# DebugCAN_v3.net
KiCad netlist of a schematic drawn in EAGLE
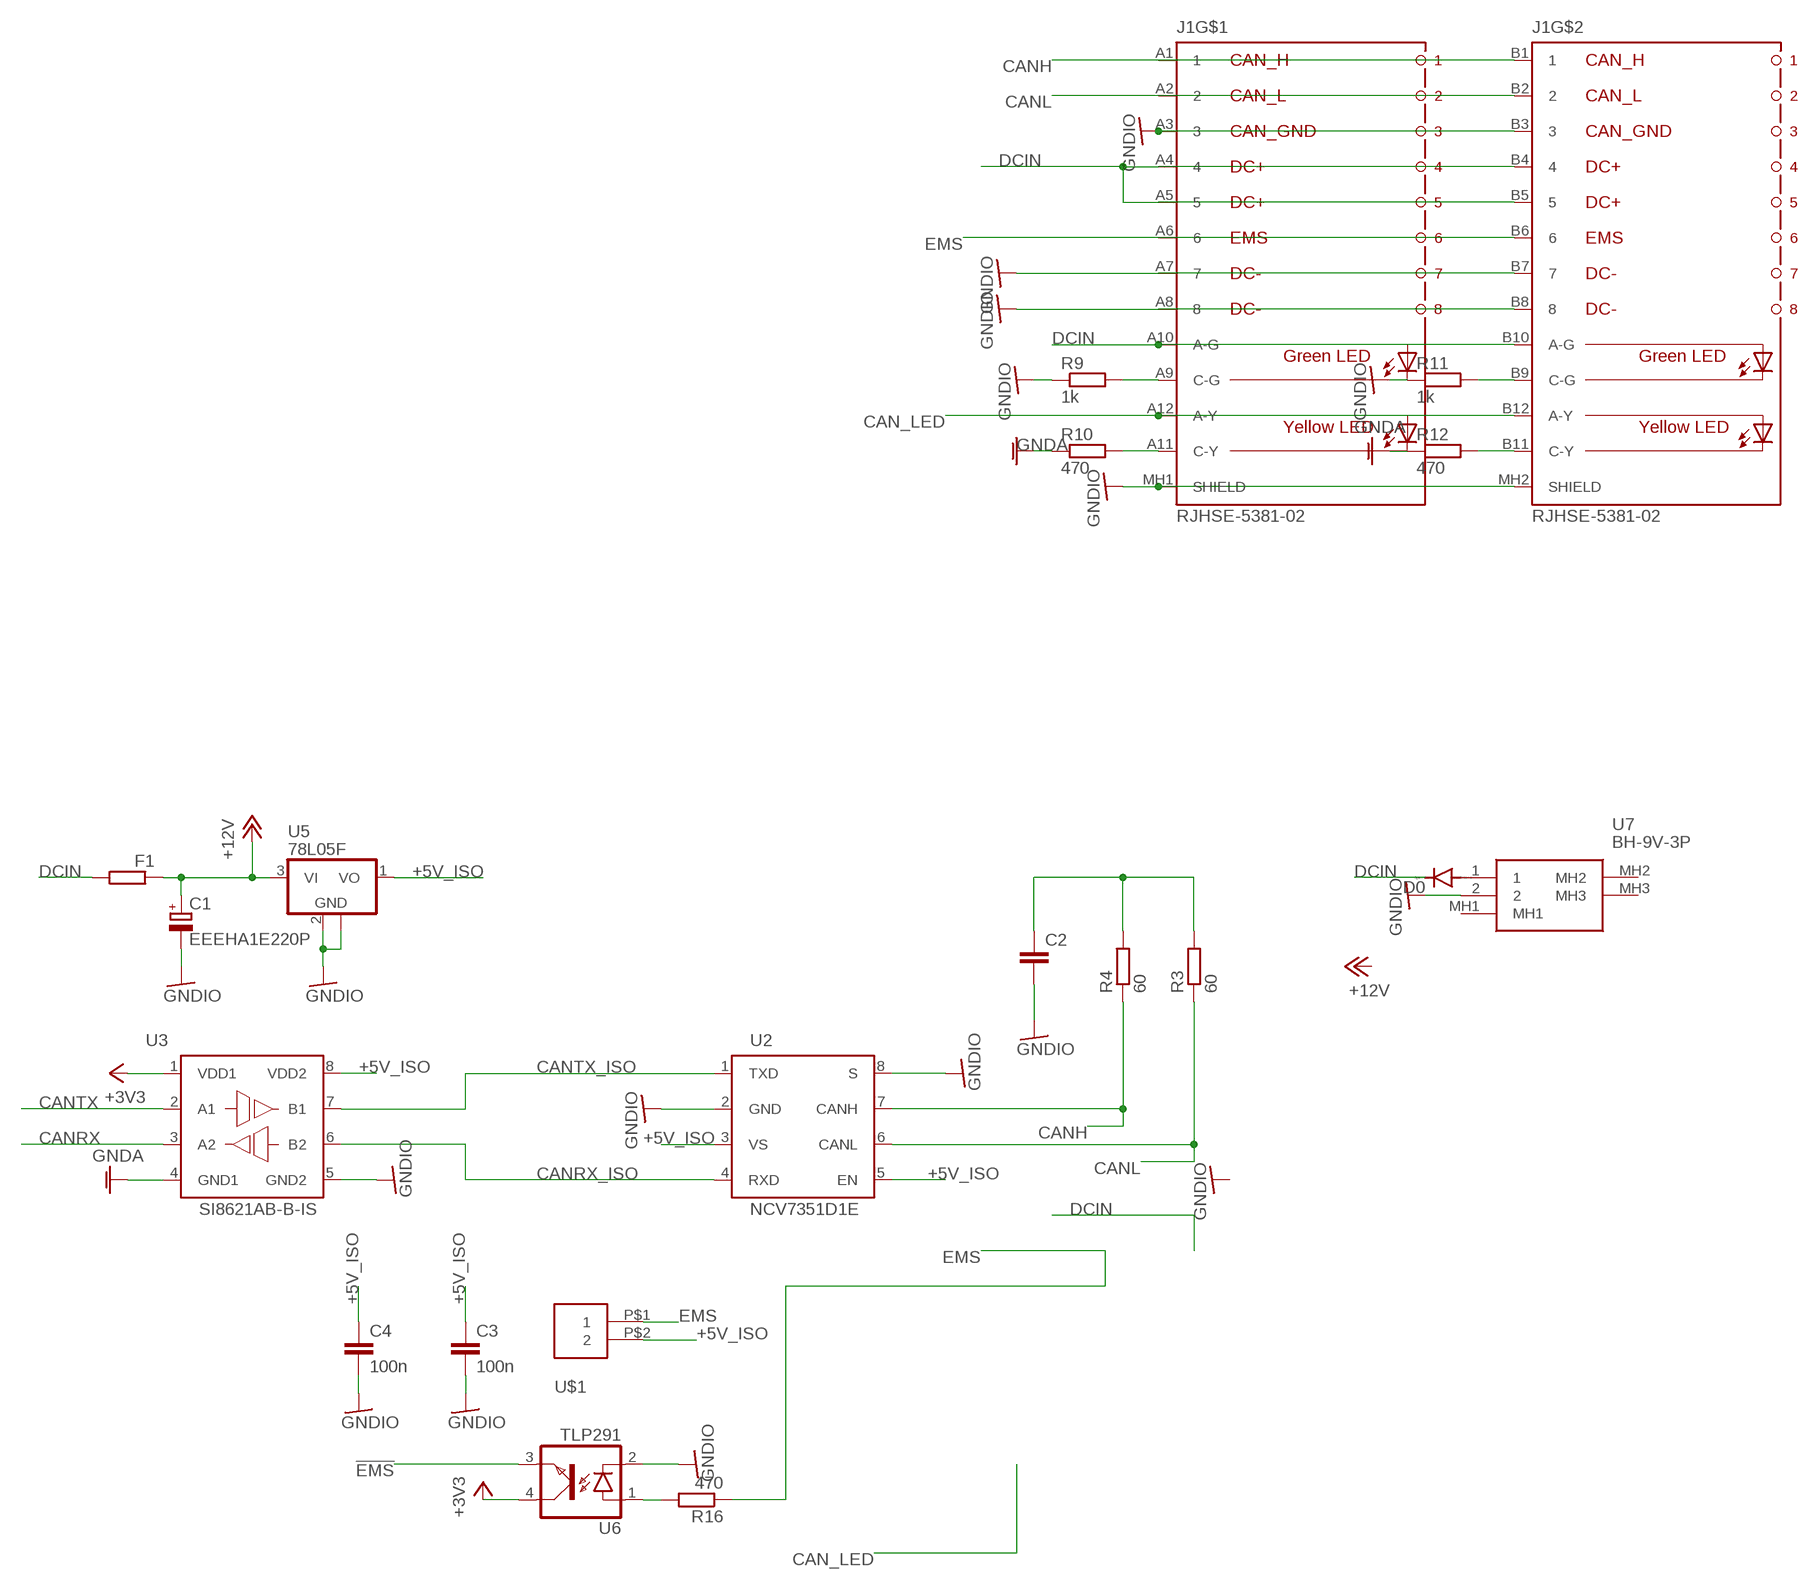
[diagram p0: schematic, sheet 1]
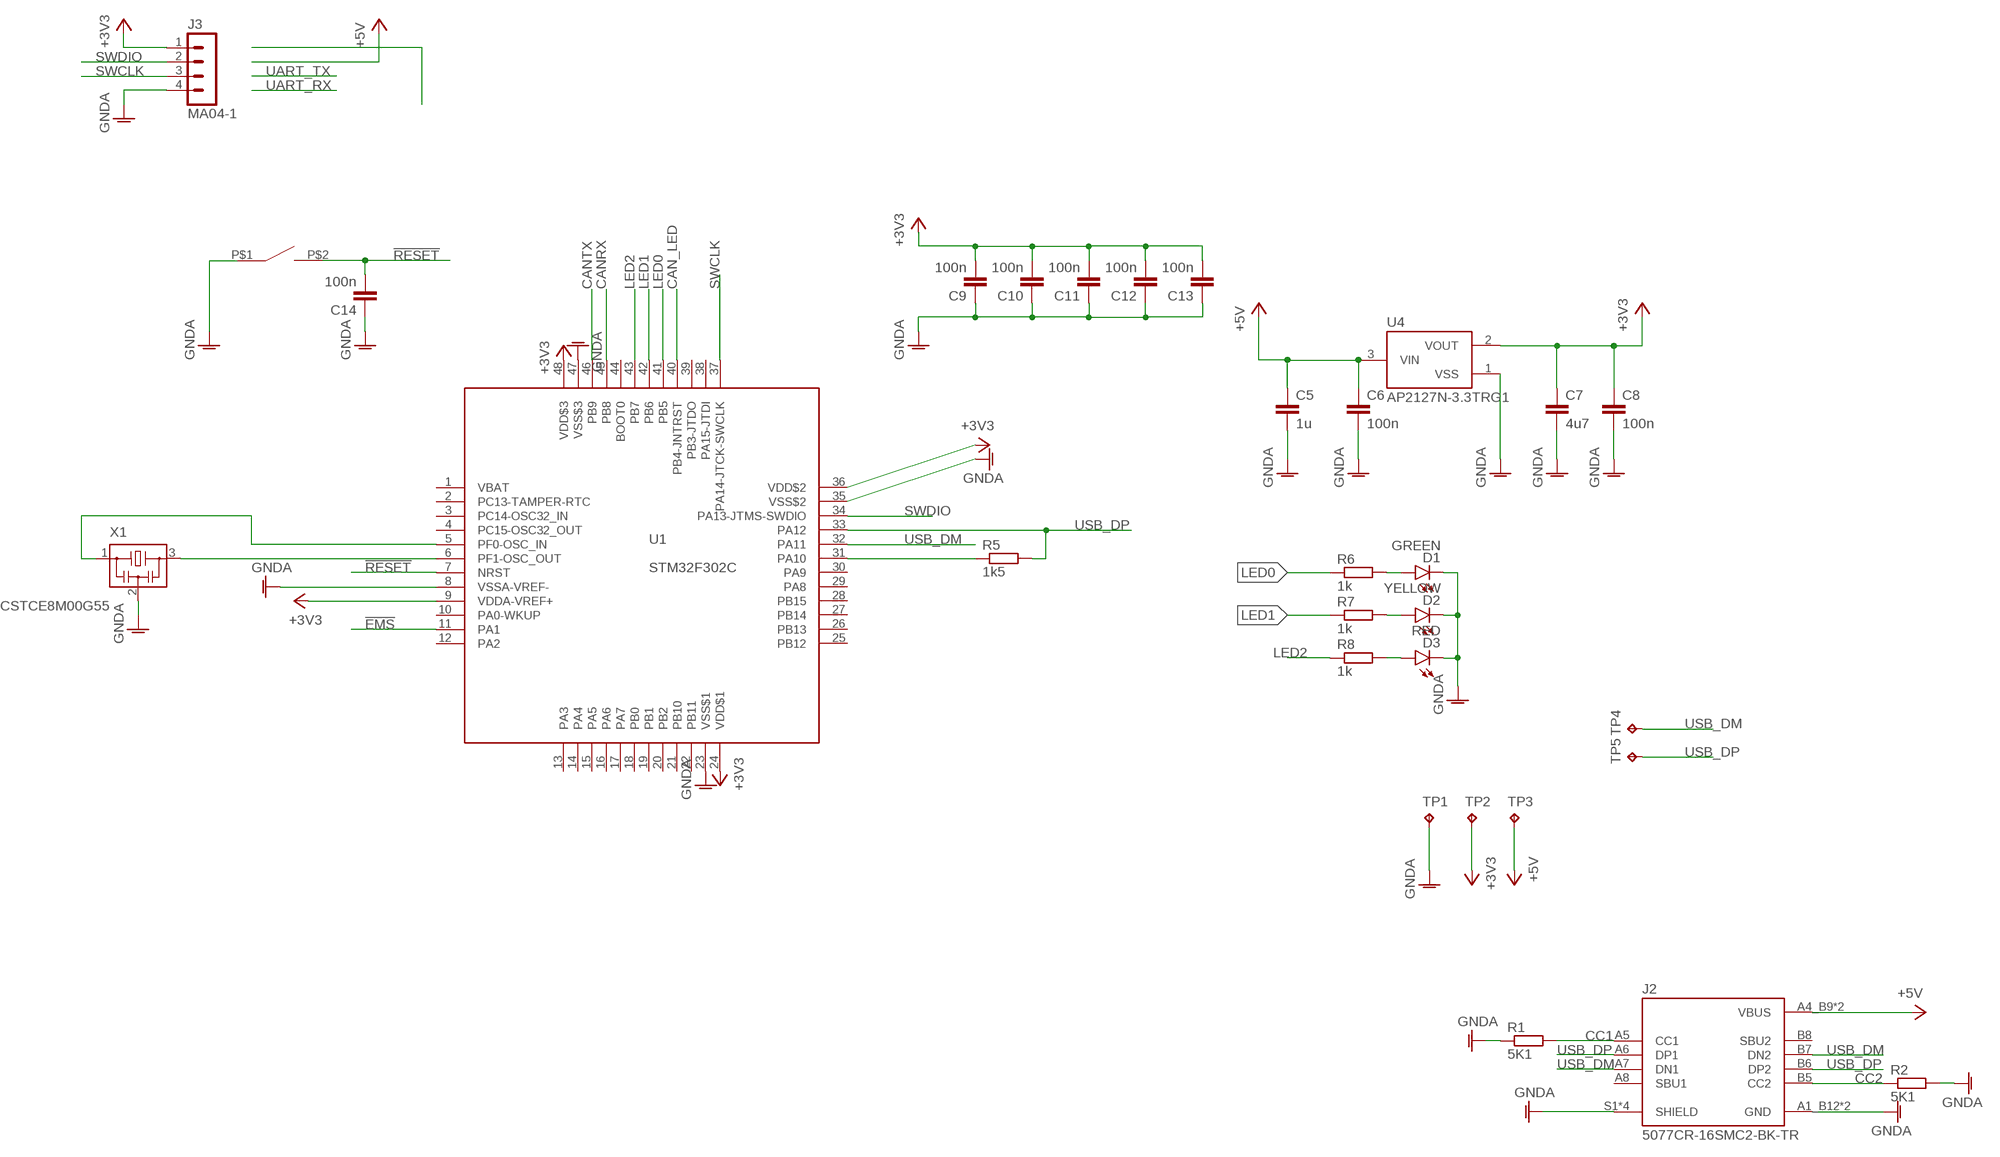
[diagram p1: schematic, sheet 2]

(export (version "E")
  (design (tool "Eeschema 10.0.6"))
  (components
    (comp (ref "C1")
      (value "EEEHA1E220P")
      (footprint "eagle-import:153CLV-0605")
      (libsource (lib "eagle-import") (part "CPOL-EU153CLV-0605"))
    )
    (comp (ref "C2")
      (value "C-EUC0603")
      (footprint "eagle-import:C0603")
      (libsource (lib "eagle-import") (part "rcl_334_C-EUC0603"))
    )
    (comp (ref "C3")
      (value "100n")
      (footprint "eagle-import:C0603")
      (libsource (lib "eagle-import") (part "rcl_334_C-EUC0603"))
    )
    (comp (ref "C4")
      (value "100n")
      (footprint "eagle-import:C0603")
      (libsource (lib "eagle-import") (part "rcl_334_C-EUC0603"))
    )
    (comp (ref "D0")
      (value "DIODE-SOD123")
      (footprint "eagle-import:SOD123")
      (libsource (lib "eagle-import") (part "DIODE-SOD123"))
    )
    (comp (ref "F1")
      (value "R-EU_R1206")
      (footprint "eagle-import:R1206")
      (libsource (lib "eagle-import") (part "rcl_334_R-EU_R1206"))
    )
    (comp (ref "J1")
      (value "RJHSE-5381-02")
      (footprint "eagle-import:RJHSE538102")
      (fields (field (name "MOUSER_PART_NUMBER") "523-RJHSE-5381-02"))
      (libsource (lib "eagle-import") (part "RJHSE-5381-02"))
    )
    (comp (ref "R3")
      (value "60")
      (footprint "eagle-import:R0603")
      (libsource (lib "eagle-import") (part "rcl_334_R-EU_R0603"))
    )
    (comp (ref "R4")
      (value "60")
      (footprint "eagle-import:R0603")
      (libsource (lib "eagle-import") (part "rcl_334_R-EU_R0603"))
    )
    (comp (ref "R9")
      (value "1k")
      (footprint "eagle-import:R0603")
      (libsource (lib "eagle-import") (part "rcl_334_R-EU_R0603"))
    )
    (comp (ref "R10")
      (value "470")
      (footprint "eagle-import:R0603")
      (libsource (lib "eagle-import") (part "rcl_334_R-EU_R0603"))
    )
    (comp (ref "R11")
      (value "1k")
      (footprint "eagle-import:R0603")
      (libsource (lib "eagle-import") (part "rcl_334_R-EU_R0603"))
    )
    (comp (ref "R12")
      (value "470")
      (footprint "eagle-import:R0603")
      (libsource (lib "eagle-import") (part "rcl_334_R-EU_R0603"))
    )
    (comp (ref "R16")
      (value "470")
      (footprint "eagle-import:R0603")
      (libsource (lib "eagle-import") (part "rcl_334_R-EU_R0603"))
    )
    (comp (ref "U$1")
      (value "XH-2-STRAIGHT")
      (footprint "eagle-import:CON-XH-2-STRAIGHT")
      (libsource (lib "eagle-import") (part "XH-2-STRAIGHT"))
    )
    (comp (ref "U2")
      (value "NCV7351D1E")
      (footprint "eagle-import:SO08")
      (libsource (lib "eagle-import") (part "NCV7351D1E"))
    )
    (comp (ref "U3")
      (value "SI8621AB-B-IS")
      (footprint "eagle-import:SO08")
      (libsource (lib "eagle-import") (part "SI8621AB-B-IS"))
    )
    (comp (ref "U5")
      (value "78L05F")
      (footprint "eagle-import:SOT89")
      (libsource (lib "eagle-import") (part "78LF05"))
    )
    (comp (ref "U6")
      (value "TLP291")
      (footprint "eagle-import:MINI-FLAT-4")
      (libsource (lib "eagle-import") (part "TLP291"))
    )
    (comp (ref "U7")
      (value "BH-9V-3P")
      (footprint "eagle-import:BH9V3P")
      (libsource (lib "eagle-import") (part "BH-9V-3P"))
    )
    (comp (ref "C5")
      (value "1u")
      (footprint "eagle-import:C0603")
      (libsource (lib "eagle-import") (part "C-EUC0603"))
    )
    (comp (ref "C6")
      (value "100n")
      (footprint "eagle-import:C0603")
      (libsource (lib "eagle-import") (part "C-EUC0603"))
    )
    (comp (ref "C7")
      (value "4u7")
      (footprint "eagle-import:C0805")
      (libsource (lib "eagle-import") (part "C-EUC0805"))
    )
    (comp (ref "C8")
      (value "100n")
      (footprint "eagle-import:C0603")
      (libsource (lib "eagle-import") (part "C-EUC0603"))
    )
    (comp (ref "C9")
      (value "100n")
      (footprint "eagle-import:C0603")
      (libsource (lib "eagle-import") (part "C-EUC0603"))
    )
    (comp (ref "C10")
      (value "100n")
      (footprint "eagle-import:C0603")
      (libsource (lib "eagle-import") (part "C-EUC0603"))
    )
    (comp (ref "C11")
      (value "100n")
      (footprint "eagle-import:C0603")
      (libsource (lib "eagle-import") (part "C-EUC0603"))
    )
    (comp (ref "C12")
      (value "100n")
      (footprint "eagle-import:C0603")
      (libsource (lib "eagle-import") (part "C-EUC0603"))
    )
    (comp (ref "C13")
      (value "100n")
      (footprint "eagle-import:C0603")
      (libsource (lib "eagle-import") (part "C-EUC0603"))
    )
    (comp (ref "C14")
      (value "100n")
      (footprint "eagle-import:C0603")
      (libsource (lib "eagle-import") (part "C-EUC0603"))
    )
    (comp (ref "D1")
      (value "GREEN")
      (footprint "eagle-import:CHIPLED_0805")
      (libsource (lib "eagle-import") (part "LEDCHIPLED_0805"))
    )
    (comp (ref "D2")
      (value "YELLOW")
      (footprint "eagle-import:CHIPLED_0805")
      (libsource (lib "eagle-import") (part "LEDCHIPLED_0805"))
    )
    (comp (ref "D3")
      (value "RED")
      (footprint "eagle-import:CHIPLED_0805")
      (libsource (lib "eagle-import") (part "LEDCHIPLED_0805"))
    )
    (comp (ref "J2")
      (value "5077CR-16SMC2-BK-TR")
      (footprint "eagle-import:NELTRON_5077CR-16SMC2-BK-TR")
      (fields (field (name "MF") "Neltron"))
      (libsource (lib "eagle-import") (part "5077CR-16SMC2-BK-TR"))
    )
    (comp (ref "J3")
      (value "MA04-1")
      (footprint "eagle-import:MA04-1")
      (libsource (lib "eagle-import") (part "MA04-1"))
    )
    (comp (ref "R1")
      (value "5K1")
      (footprint "eagle-import:R0603")
      (libsource (lib "eagle-import") (part "R-EU_R0603"))
    )
    (comp (ref "R2")
      (value "5K1")
      (footprint "eagle-import:R0603")
      (libsource (lib "eagle-import") (part "R-EU_R0603"))
    )
    (comp (ref "R5")
      (value "1k5")
      (footprint "eagle-import:R0603")
      (libsource (lib "eagle-import") (part "R-EU_R0603"))
    )
    (comp (ref "R6")
      (value "1k")
      (footprint "eagle-import:R0603")
      (libsource (lib "eagle-import") (part "R-EU_R0603"))
    )
    (comp (ref "R7")
      (value "1k")
      (footprint "eagle-import:R0603")
      (libsource (lib "eagle-import") (part "R-EU_R0603"))
    )
    (comp (ref "R8")
      (value "1k")
      (footprint "eagle-import:R0603")
      (libsource (lib "eagle-import") (part "R-EU_R0603"))
    )
    (comp (ref "S1")
      (value "SWITCH_TACTILETOP")
      (footprint "eagle-import:SWITCH_TACTILE_3X6")
      (libsource (lib "eagle-import") (part "SWITCH_TACTILETOP"))
    )
    (comp (ref "TP1")
      (value "TPB1,27")
      (footprint "eagle-import:B1,27")
      (libsource (lib "eagle-import") (part "TPB1,27"))
    )
    (comp (ref "TP2")
      (value "TPB1,27")
      (footprint "eagle-import:B1,27")
      (libsource (lib "eagle-import") (part "TPB1,27"))
    )
    (comp (ref "TP3")
      (value "TPB1,27")
      (footprint "eagle-import:B1,27")
      (libsource (lib "eagle-import") (part "TPB1,27"))
    )
    (comp (ref "TP4")
      (value "TPB1,27")
      (footprint "eagle-import:B1,27")
      (libsource (lib "eagle-import") (part "TPB1,27"))
    )
    (comp (ref "TP5")
      (value "TPB1,27")
      (footprint "eagle-import:B1,27")
      (libsource (lib "eagle-import") (part "TPB1,27"))
    )
    (comp (ref "U1")
      (value "STM32F302C")
      (footprint "eagle-import:LQFP48")
      (libsource (lib "eagle-import") (part "STM32F303C"))
    )
    (comp (ref "U4")
      (value "AP2127N-3.3TRG1")
      (footprint "eagle-import:SOT95P240X110-3")
      (libsource (lib "eagle-import") (part "XC6206"))
    )
    (comp (ref "X1")
      (value "CSTCE8M00G55")
      (footprint "eagle-import:CSTCE8M00G55")
      (libsource (lib "eagle-import") (part "CSTCE8M00G55"))
    )
  )
  (nets
    (net (code "1") (name "+3V3") (class "Default")
      (node (ref "C10") (pin "2") (pinfunction "2_2") (pintype "passive"))
      (node (ref "C11") (pin "2") (pinfunction "2_2") (pintype "passive"))
      (node (ref "C12") (pin "2") (pinfunction "2_2") (pintype "passive"))
      (node (ref "C13") (pin "2") (pinfunction "2_2") (pintype "passive"))
      (node (ref "C7") (pin "1") (pinfunction "1_1") (pintype "passive"))
      (node (ref "C8") (pin "1") (pinfunction "1_1") (pintype "passive"))
      (node (ref "C9") (pin "2") (pinfunction "2_2") (pintype "passive"))
      (node (ref "J3") (pin "1") (pinfunction "1_1") (pintype "passive"))
      (node (ref "TP2") (pin "TP") (pinfunction "TP_TP") (pintype "input"))
      (node (ref "U1") (pin "24") (pinfunction "VDD$1_24") (pintype "passive"))
      (node (ref "U1") (pin "36") (pinfunction "VDD$2_36") (pintype "passive"))
      (node (ref "U1") (pin "48") (pinfunction "VDD$3_48") (pintype "passive"))
      (node (ref "U1") (pin "9") (pinfunction "VDDA-VREF+_9") (pintype "bidirectional"))
      (node (ref "U3") (pin "1") (pinfunction "VDD1_1") (pintype "power_in"))
      (node (ref "U4") (pin "2") (pinfunction "VOUT_2") (pintype "bidirectional"))
      (node (ref "U6") (pin "4") (pinfunction "COL_4") (pintype "passive"))
    )
    (net (code "2") (name "+5V") (class "Default")
      (node (ref "C5") (pin "1") (pinfunction "1_1") (pintype "passive"))
      (node (ref "C6") (pin "1") (pinfunction "1_1") (pintype "passive"))
      (node (ref "J2") (pin "A4_B9") (pinfunction "VBUS_A4_B9") (pintype "power_in"))
      (node (ref "J2") (pin "B4_A9") (pinfunction "VBUS_B4_A9") (pintype "power_in"))
      (node (ref "TP3") (pin "TP") (pinfunction "TP_TP") (pintype "input"))
      (node (ref "U4") (pin "3") (pinfunction "VIN_3") (pintype "bidirectional"))
    )
    (net (code "3") (name "+5V_ISO") (class "Default")
      (node (ref "C3") (pin "1") (pinfunction "1_1") (pintype "passive"))
      (node (ref "C4") (pin "1") (pinfunction "1_1") (pintype "passive"))
      (node (ref "U$1") (pin "P$2") (pinfunction "2_P$2") (pintype "bidirectional"))
      (node (ref "U2") (pin "3") (pinfunction "VS_3") (pintype "power_in"))
      (node (ref "U2") (pin "5") (pinfunction "EN_5") (pintype "input"))
      (node (ref "U3") (pin "8") (pinfunction "VDD2_8") (pintype "power_in"))
      (node (ref "U5") (pin "1") (pinfunction "VO_1") (pintype "passive"))
    )
    (net (code "4") (name "+12V") (class "Default")
      (node (ref "C1") (pin "+") (pinfunction "+_+") (pintype "passive"))
      (node (ref "F1") (pin "1") (pinfunction "1_1") (pintype "passive"))
      (node (ref "U5") (pin "3") (pinfunction "VI_3") (pintype "input"))
    )
    (net (code "5") (name "CANH") (class "Default")
      (node (ref "J1") (pin "A1") (pinfunction "1_A1") (pintype "input"))
      (node (ref "J1") (pin "B1") (pinfunction "1_B1") (pintype "input"))
      (node (ref "R4") (pin "1") (pinfunction "1_1") (pintype "passive"))
      (node (ref "U2") (pin "7") (pinfunction "CANH_7") (pintype "output"))
    )
    (net (code "6") (name "CANL") (class "Default")
      (node (ref "J1") (pin "A2") (pinfunction "2_A2") (pintype "input"))
      (node (ref "J1") (pin "B2") (pinfunction "2_B2") (pintype "input"))
      (node (ref "R3") (pin "1") (pinfunction "1_1") (pintype "passive"))
      (node (ref "U2") (pin "6") (pinfunction "CANL_6") (pintype "output"))
    )
    (net (code "7") (name "CANRX") (class "Default")
      (node (ref "U1") (pin "45") (pinfunction "PB8_45") (pintype "bidirectional"))
      (node (ref "U3") (pin "3") (pinfunction "A2_3") (pintype "output"))
    )
    (net (code "8") (name "CANRX_ISO") (class "Default")
      (node (ref "U2") (pin "4") (pinfunction "RXD_4") (pintype "output"))
      (node (ref "U3") (pin "6") (pinfunction "B2_6") (pintype "output"))
    )
    (net (code "9") (name "CANTX") (class "Default")
      (node (ref "U1") (pin "46") (pinfunction "PB9_46") (pintype "bidirectional"))
      (node (ref "U3") (pin "2") (pinfunction "A1_2") (pintype "input"))
    )
    (net (code "10") (name "CANTX_ISO") (class "Default")
      (node (ref "U2") (pin "1") (pinfunction "TXD_1") (pintype "input"))
      (node (ref "U3") (pin "7") (pinfunction "B1_7") (pintype "output"))
    )
    (net (code "11") (name "CAN_LED") (class "Default")
      (node (ref "J1") (pin "A12") (pinfunction "A-Y_A12") (pintype "passive"))
      (node (ref "J1") (pin "B12") (pinfunction "A-Y_B12") (pintype "passive"))
      (node (ref "U1") (pin "40") (pinfunction "PB4-JNTRST_40") (pintype "bidirectional"))
    )
    (net (code "12") (name "CC1") (class "Default")
      (node (ref "J2") (pin "A5") (pinfunction "CC1_A5") (pintype "passive"))
      (node (ref "R1") (pin "2") (pinfunction "2_2") (pintype "passive"))
    )
    (net (code "13") (name "CC2") (class "Default")
      (node (ref "J2") (pin "B5") (pinfunction "CC2_B5") (pintype "passive"))
      (node (ref "R2") (pin "1") (pinfunction "1_1") (pintype "passive"))
    )
    (net (code "14") (name "DCIN") (class "Default")
      (node (ref "D0") (pin "C") (pinfunction "C_C") (pintype "passive"))
      (node (ref "F1") (pin "2") (pinfunction "2_2") (pintype "passive"))
      (node (ref "J1") (pin "A10") (pinfunction "A-G_A10") (pintype "passive"))
      (node (ref "J1") (pin "A4") (pinfunction "4_A4") (pintype "input"))
      (node (ref "J1") (pin "A5") (pinfunction "5_A5") (pintype "input"))
      (node (ref "J1") (pin "B10") (pinfunction "A-G_B10") (pintype "passive"))
      (node (ref "J1") (pin "B4") (pinfunction "4_B4") (pintype "input"))
      (node (ref "J1") (pin "B5") (pinfunction "5_B5") (pintype "input"))
    )
    (net (code "15") (name "EMS") (class "Default")
      (node (ref "J1") (pin "A6") (pinfunction "6_A6") (pintype "input"))
      (node (ref "J1") (pin "B6") (pinfunction "6_B6") (pintype "input"))
      (node (ref "R16") (pin "1") (pinfunction "1_1") (pintype "passive"))
      (node (ref "U$1") (pin "P$1") (pinfunction "1_P$1") (pintype "bidirectional"))
    )
    (net (code "16") (name "GNDA") (class "Default")
      (node (ref "C10") (pin "1") (pinfunction "1_1") (pintype "passive"))
      (node (ref "C11") (pin "1") (pinfunction "1_1") (pintype "passive"))
      (node (ref "C12") (pin "1") (pinfunction "1_1") (pintype "passive"))
      (node (ref "C13") (pin "1") (pinfunction "1_1") (pintype "passive"))
      (node (ref "C14") (pin "1") (pinfunction "1_1") (pintype "passive"))
      (node (ref "C5") (pin "2") (pinfunction "2_2") (pintype "passive"))
      (node (ref "C6") (pin "2") (pinfunction "2_2") (pintype "passive"))
      (node (ref "C7") (pin "2") (pinfunction "2_2") (pintype "passive"))
      (node (ref "C8") (pin "2") (pinfunction "2_2") (pintype "passive"))
      (node (ref "C9") (pin "1") (pinfunction "1_1") (pintype "passive"))
      (node (ref "D1") (pin "C") (pinfunction "C_C") (pintype "passive"))
      (node (ref "D2") (pin "C") (pinfunction "C_C") (pintype "passive"))
      (node (ref "D3") (pin "C") (pinfunction "C_C") (pintype "passive"))
      (node (ref "J2") (pin "A1_B12") (pinfunction "GND_A1_B12") (pintype "power_in"))
      (node (ref "J2") (pin "B1_A12") (pinfunction "GND_B1_A12") (pintype "power_in"))
      (node (ref "J2") (pin "S1") (pinfunction "SHIELD_S1") (pintype "passive"))
      (node (ref "J2") (pin "S2") (pinfunction "SHIELD_S2") (pintype "passive"))
      (node (ref "J2") (pin "S3") (pinfunction "SHIELD_S3") (pintype "passive"))
      (node (ref "J2") (pin "S4") (pinfunction "SHIELD_S4") (pintype "passive"))
      (node (ref "J3") (pin "4") (pinfunction "4_4") (pintype "passive"))
      (node (ref "R1") (pin "1") (pinfunction "1_1") (pintype "passive"))
      (node (ref "R10") (pin "1") (pinfunction "1_1") (pintype "passive"))
      (node (ref "R12") (pin "1") (pinfunction "1_1") (pintype "passive"))
      (node (ref "R2") (pin "2") (pinfunction "2_2") (pintype "passive"))
      (node (ref "S1") (pin "P$1") (pinfunction "1_P$1") (pintype "bidirectional"))
      (node (ref "TP1") (pin "TP") (pinfunction "TP_TP") (pintype "input"))
      (node (ref "U1") (pin "23") (pinfunction "VSS$1_23") (pintype "passive"))
      (node (ref "U1") (pin "35") (pinfunction "VSS$2_35") (pintype "passive"))
      (node (ref "U1") (pin "47") (pinfunction "VSS$3_47") (pintype "passive"))
      (node (ref "U1") (pin "8") (pinfunction "VSSA-VREF-_8") (pintype "bidirectional"))
      (node (ref "U3") (pin "4") (pinfunction "GND1_4") (pintype "power_in"))
      (node (ref "U4") (pin "1") (pinfunction "VSS_1") (pintype "bidirectional"))
      (node (ref "X1") (pin "2") (pinfunction "2_2") (pintype "passive"))
    )
    (net (code "17") (name "GNDIO") (class "Default")
      (node (ref "C1") (pin "-") (pinfunction "-_-") (pintype "passive"))
      (node (ref "C2") (pin "2") (pinfunction "2_2") (pintype "passive"))
      (node (ref "C3") (pin "2") (pinfunction "2_2") (pintype "passive"))
      (node (ref "C4") (pin "2") (pinfunction "2_2") (pintype "passive"))
      (node (ref "J1") (pin "A3") (pinfunction "3_A3") (pintype "input"))
      (node (ref "J1") (pin "A7") (pinfunction "7_A7") (pintype "input"))
      (node (ref "J1") (pin "A8") (pinfunction "8_A8") (pintype "input"))
      (node (ref "J1") (pin "B3") (pinfunction "3_B3") (pintype "input"))
      (node (ref "J1") (pin "B7") (pinfunction "7_B7") (pintype "input"))
      (node (ref "J1") (pin "B8") (pinfunction "8_B8") (pintype "input"))
      (node (ref "J1") (pin "MH1") (pinfunction "SHIELD_MH1") (pintype "passive"))
      (node (ref "J1") (pin "MH2") (pinfunction "SHIELD_MH2") (pintype "passive"))
      (node (ref "R11") (pin "1") (pinfunction "1_1") (pintype "passive"))
      (node (ref "R9") (pin "1") (pinfunction "1_1") (pintype "passive"))
      (node (ref "U2") (pin "2") (pinfunction "GND_2") (pintype "power_in"))
      (node (ref "U2") (pin "8") (pinfunction "S_8") (pintype "input"))
      (node (ref "U3") (pin "5") (pinfunction "GND2_5") (pintype "power_in"))
      (node (ref "U5") (pin "2") (pinfunction "GND_2") (pintype "passive"))
      (node (ref "U5") (pin "2@1") (pinfunction "GND_2@1") (pintype "passive"))
      (node (ref "U6") (pin "2") (pinfunction "C_2") (pintype "passive"))
      (node (ref "U7") (pin "2") (pinfunction "2_2") (pintype "bidirectional"))
    )
    (net (code "18") (name "LED0") (class "Default")
      (node (ref "R6") (pin "1") (pinfunction "1_1") (pintype "passive"))
      (node (ref "U1") (pin "41") (pinfunction "PB5_41") (pintype "bidirectional"))
    )
    (net (code "19") (name "LED1") (class "Default")
      (node (ref "R7") (pin "1") (pinfunction "1_1") (pintype "passive"))
      (node (ref "U1") (pin "42") (pinfunction "PB6_42") (pintype "bidirectional"))
    )
    (net (code "20") (name "LED2") (class "Default")
      (node (ref "R8") (pin "1") (pinfunction "1_1") (pintype "passive"))
      (node (ref "U1") (pin "43") (pinfunction "PB7_43") (pintype "bidirectional"))
    )
    (net (code "21") (name "Net-(C2-Pad1)") (class "Default")
      (node (ref "C2") (pin "1") (pinfunction "1_1") (pintype "passive"))
      (node (ref "R3") (pin "2") (pinfunction "2_2") (pintype "passive"))
      (node (ref "R4") (pin "2") (pinfunction "2_2") (pintype "passive"))
    )
    (net (code "22") (name "Net-(D0-PadA)") (class "Default")
      (node (ref "D0") (pin "A") (pinfunction "A_A") (pintype "passive"))
      (node (ref "U7") (pin "1") (pinfunction "1_1") (pintype "bidirectional"))
    )
    (net (code "23") (name "Net-(D1-PadA)") (class "Default")
      (node (ref "D1") (pin "A") (pinfunction "A_A") (pintype "passive"))
      (node (ref "R6") (pin "2") (pinfunction "2_2") (pintype "passive"))
    )
    (net (code "24") (name "Net-(D2-PadA)") (class "Default")
      (node (ref "D2") (pin "A") (pinfunction "A_A") (pintype "passive"))
      (node (ref "R7") (pin "2") (pinfunction "2_2") (pintype "passive"))
    )
    (net (code "25") (name "Net-(D3-PadA)") (class "Default")
      (node (ref "D3") (pin "A") (pinfunction "A_A") (pintype "passive"))
      (node (ref "R8") (pin "2") (pinfunction "2_2") (pintype "passive"))
    )
    (net (code "26") (name "Net-(J1A-C-G)") (class "Default")
      (node (ref "J1") (pin "A9") (pinfunction "C-G_A9") (pintype "passive"))
      (node (ref "R9") (pin "2") (pinfunction "2_2") (pintype "passive"))
    )
    (net (code "27") (name "Net-(J1A-C-Y)") (class "Default")
      (node (ref "J1") (pin "A11") (pinfunction "C-Y_A11") (pintype "passive"))
      (node (ref "R10") (pin "2") (pinfunction "2_2") (pintype "passive"))
    )
    (net (code "28") (name "Net-(J1B-C-G)") (class "Default")
      (node (ref "J1") (pin "B9") (pinfunction "C-G_B9") (pintype "passive"))
      (node (ref "R11") (pin "2") (pinfunction "2_2") (pintype "passive"))
    )
    (net (code "29") (name "Net-(J1B-C-Y)") (class "Default")
      (node (ref "J1") (pin "B11") (pinfunction "C-Y_B11") (pintype "passive"))
      (node (ref "R12") (pin "2") (pinfunction "2_2") (pintype "passive"))
    )
    (net (code "30") (name "Net-(U1-PA10)") (class "Default")
      (node (ref "R5") (pin "1") (pinfunction "1_1") (pintype "passive"))
      (node (ref "U1") (pin "31") (pinfunction "PA10_31") (pintype "bidirectional"))
    )
    (net (code "31") (name "Net-(U1-PF0-OSC_IN)") (class "Default")
      (node (ref "U1") (pin "5") (pinfunction "PF0-OSC_IN_5") (pintype "input"))
      (node (ref "X1") (pin "1") (pinfunction "1_1") (pintype "passive"))
    )
    (net (code "32") (name "Net-(U1-PF1-OSC_OUT)") (class "Default")
      (node (ref "U1") (pin "6") (pinfunction "PF1-OSC_OUT_6") (pintype "output"))
      (node (ref "X1") (pin "3") (pinfunction "3_3") (pintype "passive"))
    )
    (net (code "33") (name "Net-(U6-A)") (class "Default")
      (node (ref "R16") (pin "2") (pinfunction "2_2") (pintype "passive"))
      (node (ref "U6") (pin "1") (pinfunction "A_1") (pintype "passive"))
    )
    (net (code "34") (name "SWCLK") (class "Default")
      (node (ref "J3") (pin "3") (pinfunction "3_3") (pintype "passive"))
      (node (ref "U1") (pin "37") (pinfunction "PA14-JTCK-SWCLK_37") (pintype "bidirectional"))
    )
    (net (code "35") (name "SWDIO") (class "Default")
      (node (ref "J3") (pin "2") (pinfunction "2_2") (pintype "passive"))
      (node (ref "U1") (pin "34") (pinfunction "PA13-JTMS-SWDIO_34") (pintype "bidirectional"))
    )
    (net (code "38") (name "USB_DM") (class "Default")
      (node (ref "J2") (pin "A7") (pinfunction "DN1_A7") (pintype "passive"))
      (node (ref "J2") (pin "B7") (pinfunction "DN2_B7") (pintype "passive"))
      (node (ref "TP4") (pin "TP") (pinfunction "TP_TP") (pintype "input"))
      (node (ref "U1") (pin "32") (pinfunction "PA11_32") (pintype "bidirectional"))
    )
    (net (code "39") (name "USB_DP") (class "Default")
      (node (ref "J2") (pin "A6") (pinfunction "DP1_A6") (pintype "passive"))
      (node (ref "J2") (pin "B6") (pinfunction "DP2_B6") (pintype "passive"))
      (node (ref "R5") (pin "2") (pinfunction "2_2") (pintype "passive"))
      (node (ref "TP5") (pin "TP") (pinfunction "TP_TP") (pintype "input"))
      (node (ref "U1") (pin "33") (pinfunction "PA12_33") (pintype "bidirectional"))
    )
    (net (code "40") (name "unconnected-(J2-SBU1-PadA8)") (class "Default")
      (node (ref "J2") (pin "A8") (pinfunction "SBU1_A8") (pintype "passive"))
    )
    (net (code "41") (name "unconnected-(J2-SBU2-PadB8)") (class "Default")
      (node (ref "J2") (pin "B8") (pinfunction "SBU2_B8") (pintype "passive"))
    )
    (net (code "42") (name "unconnected-(U1-BOOT0-Pad44)") (class "Default")
      (node (ref "U1") (pin "44") (pinfunction "BOOT0_44") (pintype "input"))
    )
    (net (code "43") (name "unconnected-(U1-PA0-WKUP-Pad10)") (class "Default")
      (node (ref "U1") (pin "10") (pinfunction "PA0-WKUP_10") (pintype "bidirectional"))
    )
    (net (code "44") (name "unconnected-(U1-PA2-Pad12)") (class "Default")
      (node (ref "U1") (pin "12") (pinfunction "PA2_12") (pintype "bidirectional"))
    )
    (net (code "45") (name "unconnected-(U1-PA3-Pad13)") (class "Default")
      (node (ref "U1") (pin "13") (pinfunction "PA3_13") (pintype "bidirectional"))
    )
    (net (code "46") (name "unconnected-(U1-PA4-Pad14)") (class "Default")
      (node (ref "U1") (pin "14") (pinfunction "PA4_14") (pintype "bidirectional"))
    )
    (net (code "47") (name "unconnected-(U1-PA5-Pad15)") (class "Default")
      (node (ref "U1") (pin "15") (pinfunction "PA5_15") (pintype "bidirectional"))
    )
    (net (code "48") (name "unconnected-(U1-PA6-Pad16)") (class "Default")
      (node (ref "U1") (pin "16") (pinfunction "PA6_16") (pintype "bidirectional"))
    )
    (net (code "49") (name "unconnected-(U1-PA7-Pad17)") (class "Default")
      (node (ref "U1") (pin "17") (pinfunction "PA7_17") (pintype "bidirectional"))
    )
    (net (code "50") (name "unconnected-(U1-PA8-Pad29)") (class "Default")
      (node (ref "U1") (pin "29") (pinfunction "PA8_29") (pintype "bidirectional"))
    )
    (net (code "51") (name "unconnected-(U1-PA9-Pad30)") (class "Default")
      (node (ref "U1") (pin "30") (pinfunction "PA9_30") (pintype "bidirectional"))
    )
    (net (code "52") (name "unconnected-(U1-PA15-JTDI-Pad38)") (class "Default")
      (node (ref "U1") (pin "38") (pinfunction "PA15-JTDI_38") (pintype "bidirectional"))
    )
    (net (code "53") (name "unconnected-(U1-PB0-Pad18)") (class "Default")
      (node (ref "U1") (pin "18") (pinfunction "PB0_18") (pintype "bidirectional"))
    )
    (net (code "54") (name "unconnected-(U1-PB1-Pad19)") (class "Default")
      (node (ref "U1") (pin "19") (pinfunction "PB1_19") (pintype "bidirectional"))
    )
    (net (code "55") (name "unconnected-(U1-PB2-Pad20)") (class "Default")
      (node (ref "U1") (pin "20") (pinfunction "PB2_20") (pintype "bidirectional"))
    )
    (net (code "56") (name "unconnected-(U1-PB3-JTDO-Pad39)") (class "Default")
      (node (ref "U1") (pin "39") (pinfunction "PB3-JTDO_39") (pintype "bidirectional"))
    )
    (net (code "57") (name "unconnected-(U1-PB10-Pad21)") (class "Default")
      (node (ref "U1") (pin "21") (pinfunction "PB10_21") (pintype "bidirectional"))
    )
    (net (code "58") (name "unconnected-(U1-PB11-Pad22)") (class "Default")
      (node (ref "U1") (pin "22") (pinfunction "PB11_22") (pintype "bidirectional"))
    )
    (net (code "59") (name "unconnected-(U1-PB12-Pad25)") (class "Default")
      (node (ref "U1") (pin "25") (pinfunction "PB12_25") (pintype "bidirectional"))
    )
    (net (code "60") (name "unconnected-(U1-PB13-Pad26)") (class "Default")
      (node (ref "U1") (pin "26") (pinfunction "PB13_26") (pintype "bidirectional"))
    )
    (net (code "61") (name "unconnected-(U1-PB14-Pad27)") (class "Default")
      (node (ref "U1") (pin "27") (pinfunction "PB14_27") (pintype "bidirectional"))
    )
    (net (code "62") (name "unconnected-(U1-PB15-Pad28)") (class "Default")
      (node (ref "U1") (pin "28") (pinfunction "PB15_28") (pintype "bidirectional"))
    )
    (net (code "63") (name "unconnected-(U1-PC13-TAMPER-RTC-Pad2)") (class "Default")
      (node (ref "U1") (pin "2") (pinfunction "PC13-TAMPER-RTC_2") (pintype "bidirectional"))
    )
    (net (code "64") (name "unconnected-(U1-PC14-OSC32_IN-Pad3)") (class "Default")
      (node (ref "U1") (pin "3") (pinfunction "PC14-OSC32_IN_3") (pintype "bidirectional"))
    )
    (net (code "65") (name "unconnected-(U1-PC15-OSC32_OUT-Pad4)") (class "Default")
      (node (ref "U1") (pin "4") (pinfunction "PC15-OSC32_OUT_4") (pintype "bidirectional"))
    )
    (net (code "66") (name "unconnected-(U1-VBAT-Pad1)") (class "Default")
      (node (ref "U1") (pin "1") (pinfunction "VBAT_1") (pintype "passive"))
    )
    (net (code "67") (name "unconnected-(U7-PadMH1)") (class "Default")
      (node (ref "U7") (pin "MH1") (pinfunction "MH1_MH1") (pintype "bidirectional"))
    )
    (net (code "68") (name "unconnected-(U7-PadMH2)") (class "Default")
      (node (ref "U7") (pin "MH2") (pinfunction "MH2_MH2") (pintype "bidirectional"))
    )
    (net (code "69") (name "unconnected-(U7-PadMH3)") (class "Default")
      (node (ref "U7") (pin "MH3") (pinfunction "MH3_MH3") (pintype "bidirectional"))
    )
    (net (code "70") (name "~{EMS}") (class "Default")
      (node (ref "U1") (pin "11") (pinfunction "PA1_11") (pintype "bidirectional"))
      (node (ref "U6") (pin "3") (pinfunction "EMIT_3") (pintype "passive"))
    )
    (net (code "71") (name "~{RESET}") (class "Default")
      (node (ref "C14") (pin "2") (pinfunction "2_2") (pintype "passive"))
      (node (ref "S1") (pin "P$2") (pinfunction "2_P$2") (pintype "bidirectional"))
      (node (ref "U1") (pin "7") (pinfunction "NRST_7") (pintype "bidirectional"))
    )
  )
)
